# SipPuffOneOuputATtiny85Relays.net
KiCad netlist of a schematic drawn in EAGLE
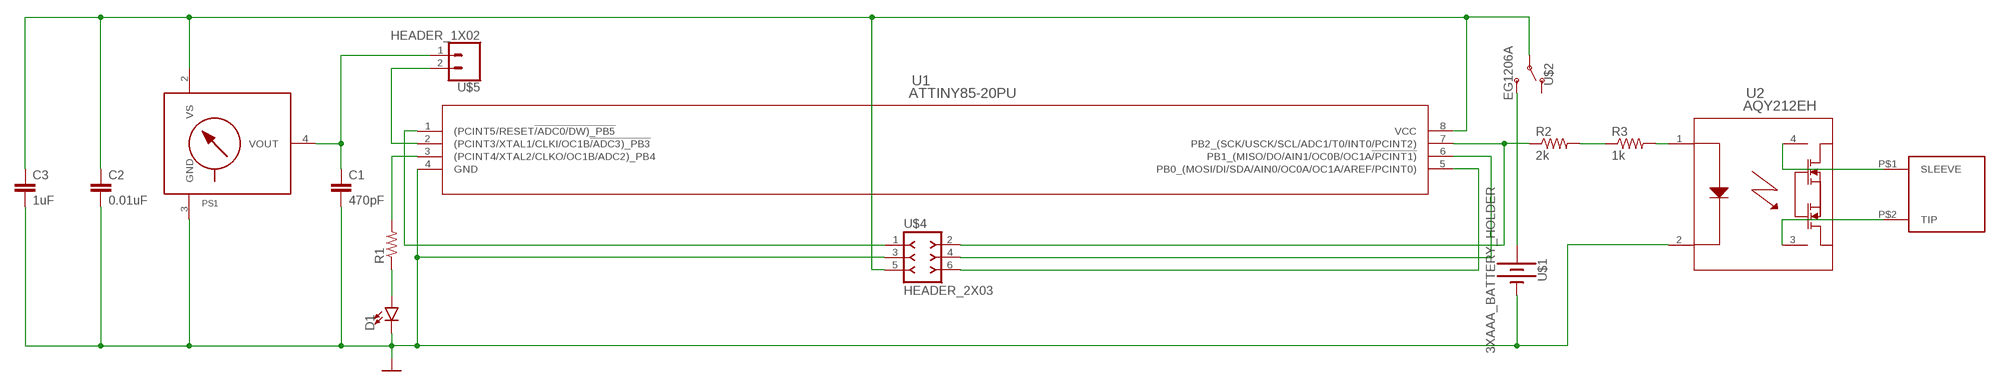
[diagram p0: schematic, sheet 1]

(export (version "E")
  (design (tool "Eeschema 10.0.6"))
  (components
    (comp (ref "C1")
      (value "470pF")
      (footprint "eagle-import:CAP-PTH-SMALL-KIT")
      (libsource (lib "eagle-import") (part "0.1UF-KIT-EZ-50V-20%"))
    )
    (comp (ref "C2")
      (value "0.01uF")
      (footprint "eagle-import:CAP-PTH-SMALL-KIT")
      (libsource (lib "eagle-import") (part "0.1UF-KIT-EZ-50V-20%"))
    )
    (comp (ref "C3")
      (value "1uF")
      (footprint "eagle-import:CAP-PTH-SMALL-KIT")
      (libsource (lib "eagle-import") (part "0.1UF-KIT-EZ-50V-20%"))
    )
    (comp (ref "D1")
      (value "LED5MM")
      (footprint "eagle-import:LED_5MM")
      (libsource (lib "eagle-import") (part "LED5MM"))
    )
    (comp (ref "PS1")
      (value "MPX-1351")
      (footprint "eagle-import:1351")
      (libsource (lib "eagle-import") (part "MPX-1351"))
    )
    (comp (ref "R1")
      (value "RESISTOR_R-US_")
      (footprint "eagle-import:RESISTOR_0207_10")
      (libsource (lib "eagle-import") (part "RESISTOR_R-US_"))
    )
    (comp (ref "R2")
      (value "2k")
      (footprint "eagle-import:RESISTOR_0207_10")
      (libsource (lib "eagle-import") (part "RESISTOR_R-US_"))
    )
    (comp (ref "R3")
      (value "1k")
      (footprint "eagle-import:RESISTOR_0207_10")
      (libsource (lib "eagle-import") (part "RESISTOR_R-US_"))
    )
    (comp (ref "U$1")
      (value "3XAAA_BATTERY_HOLDER")
      (footprint "eagle-import:3XAAA_BATTERY_HOLDER")
      (libsource (lib "eagle-import") (part "3XAAA_BATTERY_HOLDER"))
    )
    (comp (ref "U$2")
      (value "EG1206A")
      (footprint "eagle-import:EG1206A")
      (libsource (lib "eagle-import") (part "EG1206A"))
    )
    (comp (ref "U$3")
      (value "MONO_WIRE")
      (footprint "eagle-import:MONO_WIRE")
      (libsource (lib "eagle-import") (part "MONO_WIRE"))
    )
    (comp (ref "U$4")
      (value "HEADER_2X03")
      (footprint "eagle-import:2X3")
      (libsource (lib "eagle-import") (part "HEADER_2X03"))
    )
    (comp (ref "U$5")
      (value "HEADER_1X02")
      (footprint "eagle-import:1X02")
      (libsource (lib "eagle-import") (part "HEADER_1X02"))
    )
    (comp (ref "U1")
      (value "ATTINY85-20PU")
      (footprint "eagle-import:8P3")
      (fields (field (name "MANUFACTURER_PART_NUMBER") "ATTINY8520PU"))
      (libsource (lib "eagle-import") (part "ATTINY85-20PU"))
    )
    (comp (ref "U2")
      (value "AQY212EH")
      (footprint "eagle-import:PAN_AQY21-DIP4")
      (libsource (lib "eagle-import") (part "AQY212EH"))
    )
  )
  (nets
    (net (code "1") (name "GND") (class "Default")
      (node (ref "C1") (pin "2") (pinfunction "2_2") (pintype "passive"))
      (node (ref "C2") (pin "2") (pinfunction "2_2") (pintype "passive"))
      (node (ref "C3") (pin "2") (pinfunction "2_2") (pintype "passive"))
      (node (ref "D1") (pin "K") (pinfunction "C_K") (pintype "passive"))
      (node (ref "PS1") (pin "3") (pinfunction "GND_3") (pintype "power_in"))
      (node (ref "U$1") (pin "P$2") (pinfunction "-_P$2") (pintype "power_in"))
      (node (ref "U$4") (pin "3") (pinfunction "3_3") (pintype "passive"))
      (node (ref "U1") (pin "4") (pinfunction "GND_4") (pintype "power_in"))
      (node (ref "U2") (pin "2") (pinfunction "2_2") (pintype "passive"))
    )
    (net (code "2") (name "Net-(D1-PadA)") (class "Default")
      (node (ref "D1") (pin "A") (pinfunction "A_A") (pintype "passive"))
      (node (ref "R1") (pin "1") (pinfunction "1_1") (pintype "passive"))
    )
    (net (code "3") (name "Net-(PS1-VOUT)") (class "Default")
      (node (ref "C1") (pin "1") (pinfunction "1_1") (pintype "passive"))
      (node (ref "PS1") (pin "4") (pinfunction "VOUT_4") (pintype "output"))
      (node (ref "U$5") (pin "1") (pinfunction "1_1") (pintype "passive"))
    )
    (net (code "4") (name "Net-(PS1-VS)") (class "Default")
      (node (ref "C2") (pin "1") (pinfunction "1_1") (pintype "passive"))
      (node (ref "C3") (pin "1") (pinfunction "1_1") (pintype "passive"))
      (node (ref "PS1") (pin "2") (pinfunction "VS_2") (pintype "power_in"))
      (node (ref "U$2") (pin "2") (pinfunction "P_2") (pintype "passive"))
      (node (ref "U$4") (pin "5") (pinfunction "5_5") (pintype "passive"))
      (node (ref "U1") (pin "8") (pinfunction "VCC_8") (pintype "power_in"))
    )
    (net (code "5") (name "Net-(R2-Pad2)") (class "Default")
      (node (ref "R2") (pin "2") (pinfunction "2_2") (pintype "passive"))
      (node (ref "R3") (pin "1") (pinfunction "1_1") (pintype "passive"))
    )
    (net (code "6") (name "Net-(R3-Pad2)") (class "Default")
      (node (ref "R3") (pin "2") (pinfunction "2_2") (pintype "passive"))
      (node (ref "U2") (pin "1") (pinfunction "1_1") (pintype "passive"))
    )
    (net (code "7") (name "Net-(U$1-+)") (class "Default")
      (node (ref "U$1") (pin "P$1") (pinfunction "+_P$1") (pintype "power_in"))
      (node (ref "U$2") (pin "3") (pinfunction "S_3") (pintype "passive"))
    )
    (net (code "8") (name "Net-(U$3-SLEEVE)") (class "Default")
      (node (ref "U$3") (pin "P$1") (pinfunction "SLEEVE_P$1") (pintype "bidirectional"))
      (node (ref "U2") (pin "4") (pinfunction "4_4") (pintype "passive"))
    )
    (net (code "9") (name "Net-(U$3-TIP)") (class "Default")
      (node (ref "U$3") (pin "P$2") (pinfunction "TIP_P$2") (pintype "bidirectional"))
      (node (ref "U2") (pin "3") (pinfunction "3_3") (pintype "passive"))
    )
    (net (code "10") (name "Net-(U1-(PCINT3{slash}XTAL1{slash}CLKI{slash}OC1B~{{slash}ADC3})_PB3)") (class "Default")
      (node (ref "U$5") (pin "2") (pinfunction "2_2") (pintype "passive"))
      (node (ref "U1") (pin "2") (pinfunction "(PCINT3/XTAL1/CLKI/OC1B~{/ADC3})_PB3_2") (pintype "bidirectional"))
    )
    (net (code "11") (name "Net-(U1-(PCINT4{slash}XTAL2{slash}CLKO{slash}OC1B{slash}ADC2)_PB4)") (class "Default")
      (node (ref "R1") (pin "2") (pinfunction "2_2") (pintype "passive"))
      (node (ref "U1") (pin "3") (pinfunction "(PCINT4/XTAL2/CLKO/OC1B/ADC2)_PB4_3") (pintype "bidirectional"))
    )
    (net (code "12") (name "Net-(U1-(PCINT5{slash}RESET~{{slash}ADC0{slash}DW})_PB5)") (class "Default")
      (node (ref "U$4") (pin "1") (pinfunction "1_1") (pintype "passive"))
      (node (ref "U1") (pin "1") (pinfunction "(PCINT5/RESET~{/ADC0/DW})_PB5_1") (pintype "bidirectional"))
    )
    (net (code "13") (name "Net-(U1-PB0_(MOSI{slash}DI{slash}SDA{slash}AIN0{slash}OC0A{slash}OC1A{slash}AREF{slash}PCINT0))") (class "Default")
      (node (ref "U$4") (pin "6") (pinfunction "6_6") (pintype "passive"))
      (node (ref "U1") (pin "5") (pinfunction "PB0_(MOSI/DI/SDA/AIN0/OC0A/OC1A/AREF/PCINT0)_5") (pintype "bidirectional"))
    )
    (net (code "14") (name "Net-(U1-PB1_(MISO{slash}DO{slash}AIN1{slash}OC0B{slash}OC1A~{{slash}PCINT1}))") (class "Default")
      (node (ref "U$4") (pin "4") (pinfunction "4_4") (pintype "passive"))
      (node (ref "U1") (pin "6") (pinfunction "PB1_(MISO/DO/AIN1/OC0B/OC1A~{/PCINT1})_6") (pintype "bidirectional"))
    )
    (net (code "15") (name "Net-(U1-PB2_(SCK{slash}USCK{slash}SCL{slash}ADC1{slash}T0{slash}INT0{slash}PCINT2))") (class "Default")
      (node (ref "R2") (pin "1") (pinfunction "1_1") (pintype "passive"))
      (node (ref "U$4") (pin "2") (pinfunction "2_2") (pintype "passive"))
      (node (ref "U1") (pin "7") (pinfunction "PB2_(SCK/USCK/SCL/ADC1/T0/INT0/PCINT2)_7") (pintype "bidirectional"))
    )
    (net (code "16") (name "unconnected-(PS1-NC-Pad1)") (class "Default")
      (node (ref "PS1") (pin "1") (pinfunction "NC_1") (pintype "no_connect"))
    )
    (net (code "17") (name "unconnected-(PS1-NC-Pad5)") (class "Default")
      (node (ref "PS1") (pin "5") (pinfunction "NC_5") (pintype "no_connect"))
    )
    (net (code "18") (name "unconnected-(PS1-NC-Pad6)") (class "Default")
      (node (ref "PS1") (pin "6") (pinfunction "NC_6") (pintype "no_connect"))
    )
    (net (code "19") (name "unconnected-(U$2-O-Pad1)") (class "Default")
      (node (ref "U$2") (pin "1") (pinfunction "O_1") (pintype "passive"))
    )
  )
)
